# LED_GREEN_0603x8.net
KiCad netlist of a schematic drawn in Altium Designer
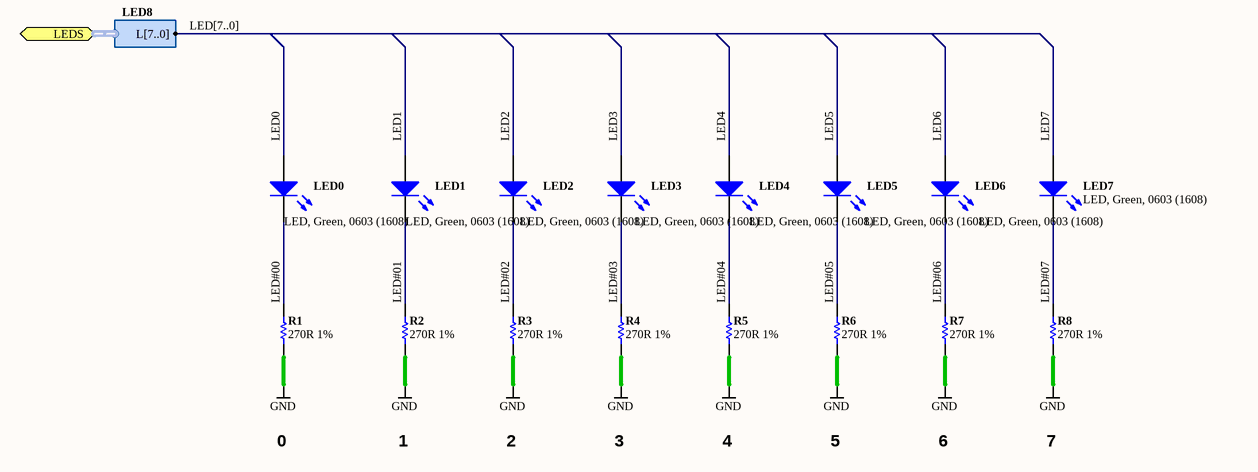
[diagram p0: LED_GREEN_0603x8.SCHDOC]

(export (version "E")
  (design (tool "Eeschema 10.0.6"))
  (components
    (comp (ref "LED0")
      (value "LED, Green, 0603 (1608)")
      (footprint "0603LED")
      (libsource (lib "AltiumDesignLibrary") (part "DIO-LED-1S"))
    )
    (comp (ref "LED1")
      (value "LED, Green, 0603 (1608)")
      (footprint "0603LED")
      (libsource (lib "AltiumDesignLibrary") (part "DIO-LED-1S"))
    )
    (comp (ref "LED2")
      (value "LED, Green, 0603 (1608)")
      (footprint "0603LED")
      (libsource (lib "AltiumDesignLibrary") (part "DIO-LED-1S"))
    )
    (comp (ref "LED3")
      (value "LED, Green, 0603 (1608)")
      (footprint "0603LED")
      (libsource (lib "AltiumDesignLibrary") (part "DIO-LED-1S"))
    )
    (comp (ref "LED4")
      (value "LED, Green, 0603 (1608)")
      (footprint "0603LED")
      (libsource (lib "AltiumDesignLibrary") (part "DIO-LED-1S"))
    )
    (comp (ref "LED5")
      (value "LED, Green, 0603 (1608)")
      (footprint "0603LED")
      (libsource (lib "AltiumDesignLibrary") (part "DIO-LED-1S"))
    )
    (comp (ref "LED6")
      (value "LED, Green, 0603 (1608)")
      (footprint "0603LED")
      (libsource (lib "AltiumDesignLibrary") (part "DIO-LED-1S"))
    )
    (comp (ref "LED7")
      (value "LED, Green, 0603 (1608)")
      (footprint "0603LED")
      (libsource (lib "AltiumDesignLibrary") (part "DIO-LED-1S"))
    )
    (comp (ref "R1")
      (value "270R 1%")
      (footprint "RESC1005-STAR")
      (description "Resistor, 270R 1% 0402 (1005)")
      (fields (field (name "TOLERANCE") "1 %"))
      (libsource (lib "altium-import") (part "root_2_RES_"))
    )
    (comp (ref "R2")
      (value "270R 1%")
      (footprint "RESC1005-STAR")
      (description "Resistor, 270R 1% 0402 (1005)")
      (fields (field (name "TOLERANCE") "1 %"))
      (libsource (lib "altium-import") (part "root_2_RES_"))
    )
    (comp (ref "R3")
      (value "270R 1%")
      (footprint "RESC1005-STAR")
      (description "Resistor, 270R 1% 0402 (1005)")
      (fields (field (name "TOLERANCE") "1 %"))
      (libsource (lib "altium-import") (part "root_2_RES_"))
    )
    (comp (ref "R4")
      (value "270R 1%")
      (footprint "RESC1005-STAR")
      (description "Resistor, 270R 1% 0402 (1005)")
      (fields (field (name "TOLERANCE") "1 %"))
      (libsource (lib "altium-import") (part "root_2_RES_"))
    )
    (comp (ref "R5")
      (value "270R 1%")
      (footprint "RESC1005-STAR")
      (description "Resistor, 270R 1% 0402 (1005)")
      (fields (field (name "TOLERANCE") "1 %"))
      (libsource (lib "altium-import") (part "root_2_RES_"))
    )
    (comp (ref "R6")
      (value "270R 1%")
      (footprint "RESC1005-STAR")
      (description "Resistor, 270R 1% 0402 (1005)")
      (fields (field (name "TOLERANCE") "1 %"))
      (libsource (lib "altium-import") (part "root_2_RES_"))
    )
    (comp (ref "R7")
      (value "270R 1%")
      (footprint "RESC1005-STAR")
      (description "Resistor, 270R 1% 0402 (1005)")
      (fields (field (name "TOLERANCE") "1 %"))
      (libsource (lib "altium-import") (part "root_2_RES_"))
    )
    (comp (ref "R8")
      (value "270R 1%")
      (footprint "RESC1005-STAR")
      (description "Resistor, 270R 1% 0402 (1005)")
      (fields (field (name "TOLERANCE") "1 %"))
      (libsource (lib "altium-import") (part "root_2_RES_"))
    )
  )
  (nets
    (net (code "2") (name "/LED#00") (class "Default")
      (node (ref "LED0") (pin "2") (pinfunction "K_2") (pintype "passive"))
      (node (ref "R1") (pin "2") (pinfunction "2_2") (pintype "passive"))
    )
    (net (code "3") (name "/LED#01") (class "Default")
      (node (ref "LED1") (pin "2") (pinfunction "K_2") (pintype "passive"))
      (node (ref "R2") (pin "2") (pinfunction "2_2") (pintype "passive"))
    )
    (net (code "4") (name "/LED#02") (class "Default")
      (node (ref "LED2") (pin "2") (pinfunction "K_2") (pintype "passive"))
      (node (ref "R3") (pin "2") (pinfunction "2_2") (pintype "passive"))
    )
    (net (code "5") (name "/LED#03") (class "Default")
      (node (ref "LED3") (pin "2") (pinfunction "K_2") (pintype "passive"))
      (node (ref "R4") (pin "2") (pinfunction "2_2") (pintype "passive"))
    )
    (net (code "6") (name "/LED#04") (class "Default")
      (node (ref "LED4") (pin "2") (pinfunction "K_2") (pintype "passive"))
      (node (ref "R5") (pin "2") (pinfunction "2_2") (pintype "passive"))
    )
    (net (code "7") (name "/LED#05") (class "Default")
      (node (ref "LED5") (pin "2") (pinfunction "K_2") (pintype "passive"))
      (node (ref "R6") (pin "2") (pinfunction "2_2") (pintype "passive"))
    )
    (net (code "8") (name "/LED#06") (class "Default")
      (node (ref "LED6") (pin "2") (pinfunction "K_2") (pintype "passive"))
      (node (ref "R7") (pin "2") (pinfunction "2_2") (pintype "passive"))
    )
    (net (code "9") (name "/LED#07") (class "Default")
      (node (ref "LED7") (pin "2") (pinfunction "K_2") (pintype "passive"))
      (node (ref "R8") (pin "2") (pinfunction "2_2") (pintype "passive"))
    )
    (net (code "10") (name "/LED0") (class "Default")
      (node (ref "LED0") (pin "1") (pinfunction "A_1") (pintype "passive"))
    )
    (net (code "11") (name "/LED1") (class "Default")
      (node (ref "LED1") (pin "1") (pinfunction "A_1") (pintype "passive"))
    )
    (net (code "12") (name "/LED2") (class "Default")
      (node (ref "LED2") (pin "1") (pinfunction "A_1") (pintype "passive"))
    )
    (net (code "13") (name "/LED3") (class "Default")
      (node (ref "LED3") (pin "1") (pinfunction "A_1") (pintype "passive"))
    )
    (net (code "14") (name "/LED4") (class "Default")
      (node (ref "LED4") (pin "1") (pinfunction "A_1") (pintype "passive"))
    )
    (net (code "15") (name "/LED5") (class "Default")
      (node (ref "LED5") (pin "1") (pinfunction "A_1") (pintype "passive"))
    )
    (net (code "16") (name "/LED6") (class "Default")
      (node (ref "LED6") (pin "1") (pinfunction "A_1") (pintype "passive"))
    )
    (net (code "17") (name "/LED7") (class "Default")
      (node (ref "LED7") (pin "1") (pinfunction "A_1") (pintype "passive"))
    )
    (net (code "20") (name "GND") (class "Default")
      (node (ref "R1") (pin "1") (pinfunction "1_1") (pintype "passive"))
      (node (ref "R2") (pin "1") (pinfunction "1_1") (pintype "passive"))
      (node (ref "R3") (pin "1") (pinfunction "1_1") (pintype "passive"))
      (node (ref "R4") (pin "1") (pinfunction "1_1") (pintype "passive"))
      (node (ref "R5") (pin "1") (pinfunction "1_1") (pintype "passive"))
      (node (ref "R6") (pin "1") (pinfunction "1_1") (pintype "passive"))
      (node (ref "R7") (pin "1") (pinfunction "1_1") (pintype "passive"))
      (node (ref "R8") (pin "1") (pinfunction "1_1") (pintype "passive"))
    )
  )
)
